# CPLD.net
KiCad netlist of a schematic drawn in Altium Designer
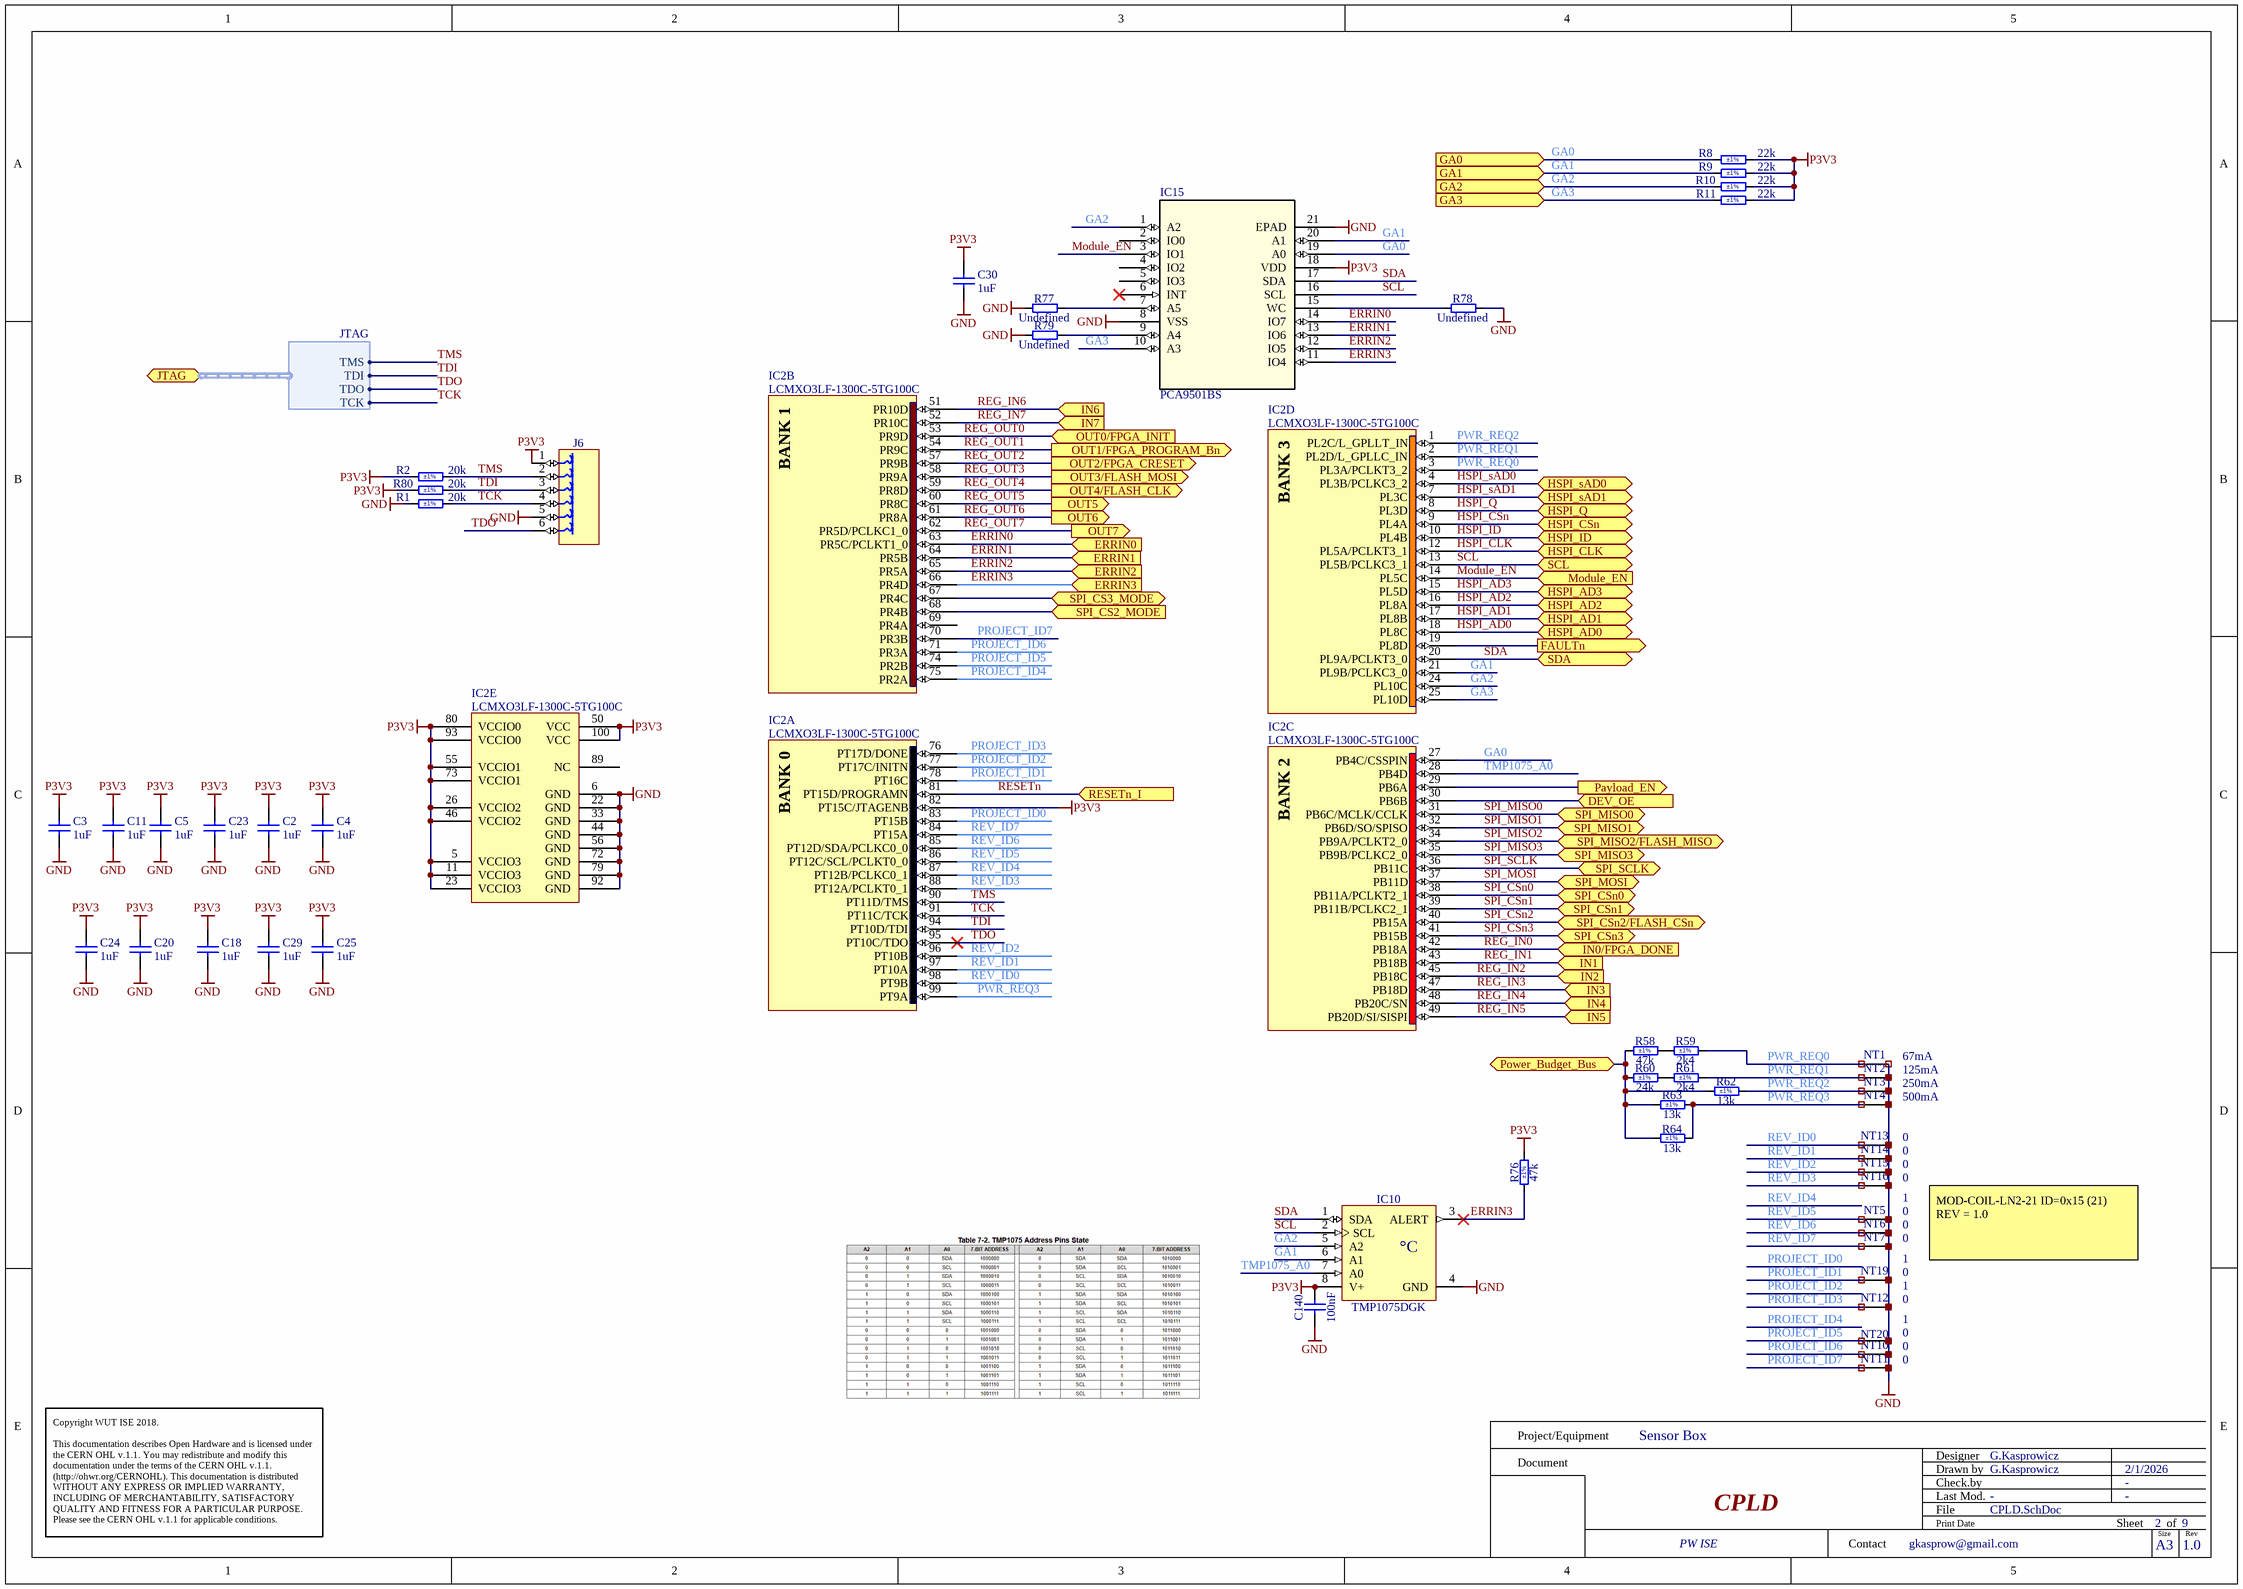
[diagram p0: CPLD.SchDoc]

(export (version "E")
  (design (tool "Eeschema 10.0.6"))
  (components
    (comp (ref "C2")
      (value "1uF")
      (footprint "CAPC1005X55N")
      (description "Non-polarised capacitor")
      (fields
        (field (name "PART NUMBER") "CC0402_1UF_16V_10%_X5R")
        (field (name "VOLTAGE") "16V")
        (field (name "AUTHOR") "CERN DEM JLC")
      )
      (libsource (lib "Capacitors") (part "Capacitor - non polarized"))
    )
    (comp (ref "C3")
      (value "1uF")
      (footprint "CAPC1005X55N")
      (description "Non-polarised capacitor")
      (fields
        (field (name "PART NUMBER") "CC0402_1UF_16V_10%_X5R")
        (field (name "VOLTAGE") "16V")
        (field (name "AUTHOR") "CERN DEM JLC")
      )
      (libsource (lib "Capacitors") (part "Capacitor - non polarized"))
    )
    (comp (ref "C4")
      (value "1uF")
      (footprint "CAPC1005X55N")
      (description "Non-polarised capacitor")
      (fields
        (field (name "PART NUMBER") "CC0402_1UF_16V_10%_X5R")
        (field (name "VOLTAGE") "16V")
        (field (name "AUTHOR") "CERN DEM JLC")
      )
      (libsource (lib "Capacitors") (part "Capacitor - non polarized"))
    )
    (comp (ref "C5")
      (value "1uF")
      (footprint "CAPC1005X55N")
      (description "Non-polarised capacitor")
      (fields
        (field (name "PART NUMBER") "CC0402_1UF_16V_10%_X5R")
        (field (name "VOLTAGE") "16V")
        (field (name "AUTHOR") "CERN DEM JLC")
      )
      (libsource (lib "Capacitors") (part "Capacitor - non polarized"))
    )
    (comp (ref "C11")
      (value "1uF")
      (footprint "CAPC1005X55N")
      (description "Non-polarised capacitor")
      (fields
        (field (name "PART NUMBER") "CC0402_1UF_16V_10%_X5R")
        (field (name "VOLTAGE") "16V")
        (field (name "AUTHOR") "CERN DEM JLC")
      )
      (libsource (lib "Capacitors") (part "Capacitor - non polarized"))
    )
    (comp (ref "C18")
      (value "1uF")
      (footprint "CAPC1005X55N")
      (description "Non-polarised capacitor")
      (fields
        (field (name "PART NUMBER") "CC0402_1UF_16V_10%_X5R")
        (field (name "VOLTAGE") "16V")
        (field (name "AUTHOR") "CERN DEM JLC")
      )
      (libsource (lib "Capacitors") (part "Capacitor - non polarized"))
    )
    (comp (ref "C20")
      (value "1uF")
      (footprint "CAPC1005X55N")
      (description "Non-polarised capacitor")
      (fields
        (field (name "PART NUMBER") "CC0402_1UF_16V_10%_X5R")
        (field (name "VOLTAGE") "16V")
        (field (name "AUTHOR") "CERN DEM JLC")
      )
      (libsource (lib "Capacitors") (part "Capacitor - non polarized"))
    )
    (comp (ref "C23")
      (value "1uF")
      (footprint "CAPC1005X55N")
      (description "Non-polarised capacitor")
      (fields
        (field (name "PART NUMBER") "CC0402_1UF_16V_10%_X5R")
        (field (name "VOLTAGE") "16V")
        (field (name "AUTHOR") "CERN DEM JLC")
      )
      (libsource (lib "Capacitors") (part "Capacitor - non polarized"))
    )
    (comp (ref "C24")
      (value "1uF")
      (footprint "CAPC1005X55N")
      (description "Non-polarised capacitor")
      (fields
        (field (name "PART NUMBER") "CC0402_1UF_16V_10%_X5R")
        (field (name "VOLTAGE") "16V")
        (field (name "AUTHOR") "CERN DEM JLC")
      )
      (libsource (lib "Capacitors") (part "Capacitor - non polarized"))
    )
    (comp (ref "C25")
      (value "1uF")
      (footprint "CAPC1005X55N")
      (description "Non-polarised capacitor")
      (fields
        (field (name "PART NUMBER") "CC0402_1UF_16V_10%_X5R")
        (field (name "VOLTAGE") "16V")
        (field (name "AUTHOR") "CERN DEM JLC")
      )
      (libsource (lib "Capacitors") (part "Capacitor - non polarized"))
    )
    (comp (ref "C29")
      (value "1uF")
      (footprint "CAPC1005X55N")
      (description "Non-polarised capacitor")
      (fields
        (field (name "PART NUMBER") "CC0402_1UF_16V_10%_X5R")
        (field (name "VOLTAGE") "16V")
        (field (name "AUTHOR") "CERN DEM JLC")
      )
      (libsource (lib "Capacitors") (part "Capacitor - non polarized"))
    )
    (comp (ref "C30")
      (value "1uF")
      (footprint "CAPC1005X55N")
      (description "Non-polarised capacitor")
      (fields
        (field (name "PART NUMBER") "CC0402_1UF_16V_10%_X5R")
        (field (name "VOLTAGE") "16V")
        (field (name "AUTHOR") "CERN DEM JLC")
      )
      (libsource (lib "Capacitors") (part "Capacitor - non polarized"))
    )
    (comp (ref "C140")
      (value "100nF")
      (footprint "CAPC1005X55N")
      (description "Non-polarised capacitor")
      (fields
        (field (name "PART NUMBER") "CC0402_100NF_16V_10%_X7R")
        (field (name "VOLTAGE") "16V")
        (field (name "AUTHOR") "CERN DEM JLC")
      )
      (libsource (lib "Capacitors") (part "Capacitor - non polarized"))
    )
    (comp (ref "IC2")
      (value "LCMXO3LF-1300C-5TG100C")
      (footprint "QFP50P1600X1600X160-100N")
      (fields (field (name "MANUFACTURER") "LATTICE SEMICONDUCTOR") (field (name "AUTHOR") "CERN DEM MR"))
      (libsource (lib "ICs And Semiconductors") (part "LCMXO3LF-1300C-5TG100"))
    )
    (comp (ref "IC10")
      (value "TMP1075DGK")
      (footprint "SOP65P490X110-8N")
      (description "High Accuracy Temperature Sensor With I2C and SMBus Interface in Industry Standard LM75")
      (fields (field (name "MANUFACTURER") "TEXAS INSTRUMENTS") (field (name "AUTHOR") "CERN DEM MR"))
      (libsource (lib "ICs And Semiconductors") (part "TMP1075"))
    )
    (comp (ref "IC15")
      (value "PCA9501BS")
      (footprint "HVQFN20_SOT662-1_5X5_NXP")
      (description "8-bit I2C-bus and SMBus I/O port with interrupt, 2-kbit\r\nEEPROM and 6 address pins")
      (fields (field (name "MANUFACTURER") "NXP") (field (name "MANUFACTURER PART NUMBER") "PCA9501BS,118"))
      (libsource (lib "ICs_Analog_Interfaces") (part "IFC_PCA9501BS"))
    )
    (comp (ref "J6")
      (value "TC2030-MCP")
      (footprint "TC2030-MCP")
      (description "TC2030-MCP and TC2030-MCP-NL Pad Contact")
      (fields (field (name "AUTHOR") "CERN DEM HF"))
      (libsource (lib "Eletro-mechanical") (part "TC2030-MCP"))
    )
    (comp (ref "NT1")
      (value "Net Tie")
      (footprint "Net Tie 3")
      (fields (field (name "PART NUMBER") "Net Tie 3") (field (name "AUTHOR") "CERN DEM HF"))
      (libsource (lib "Eletro-mechanical") (part "Net Tie_a"))
    )
    (comp (ref "NT2")
      (value "Net Tie")
      (footprint "Net Tie 3")
      (fields (field (name "PART NUMBER") "Net Tie 3") (field (name "AUTHOR") "CERN DEM HF"))
      (libsource (lib "Eletro-mechanical") (part "Net Tie_a"))
    )
    (comp (ref "NT3")
      (value "Net Tie")
      (footprint "Net Tie 3")
      (fields (field (name "PART NUMBER") "Net Tie 3") (field (name "AUTHOR") "CERN DEM HF"))
      (libsource (lib "Eletro-mechanical") (part "Net Tie_a"))
    )
    (comp (ref "NT4")
      (value "Net Tie")
      (footprint "Net Tie 3")
      (fields (field (name "PART NUMBER") "Net Tie 3") (field (name "AUTHOR") "CERN DEM HF"))
      (libsource (lib "Eletro-mechanical") (part "Net Tie_a"))
    )
    (comp (ref "NT5")
      (value "Net Tie")
      (footprint "Net Tie 3")
      (fields (field (name "PART NUMBER") "Net Tie 3") (field (name "AUTHOR") "CERN DEM HF"))
      (libsource (lib "Eletro-mechanical") (part "Net Tie_a"))
    )
    (comp (ref "NT6")
      (value "Net Tie")
      (footprint "Net Tie 3")
      (fields (field (name "PART NUMBER") "Net Tie 3") (field (name "AUTHOR") "CERN DEM HF"))
      (libsource (lib "Eletro-mechanical") (part "Net Tie_a"))
    )
    (comp (ref "NT7")
      (value "Net Tie")
      (footprint "Net Tie 3")
      (fields (field (name "PART NUMBER") "Net Tie 3") (field (name "AUTHOR") "CERN DEM HF"))
      (libsource (lib "Eletro-mechanical") (part "Net Tie_a"))
    )
    (comp (ref "NT10")
      (value "Net Tie")
      (footprint "Net Tie 3")
      (fields (field (name "PART NUMBER") "Net Tie 3") (field (name "AUTHOR") "CERN DEM HF"))
      (libsource (lib "Eletro-mechanical") (part "Net Tie_a"))
    )
    (comp (ref "NT11")
      (value "Net Tie")
      (footprint "Net Tie 3")
      (fields (field (name "PART NUMBER") "Net Tie 3") (field (name "AUTHOR") "CERN DEM HF"))
      (libsource (lib "Eletro-mechanical") (part "Net Tie_a"))
    )
    (comp (ref "NT12")
      (value "Net Tie")
      (footprint "Net Tie 3")
      (fields (field (name "PART NUMBER") "Net Tie 3") (field (name "AUTHOR") "CERN DEM HF"))
      (libsource (lib "Eletro-mechanical") (part "Net Tie_a"))
    )
    (comp (ref "NT13")
      (value "Net Tie")
      (footprint "Net Tie 3")
      (fields (field (name "PART NUMBER") "Net Tie 3") (field (name "AUTHOR") "CERN DEM HF"))
      (libsource (lib "Eletro-mechanical") (part "Net Tie_a"))
    )
    (comp (ref "NT14")
      (value "Net Tie")
      (footprint "Net Tie 3")
      (fields (field (name "PART NUMBER") "Net Tie 3") (field (name "AUTHOR") "CERN DEM HF"))
      (libsource (lib "Eletro-mechanical") (part "Net Tie_a"))
    )
    (comp (ref "NT15")
      (value "Net Tie")
      (footprint "Net Tie 3")
      (fields (field (name "PART NUMBER") "Net Tie 3") (field (name "AUTHOR") "CERN DEM HF"))
      (libsource (lib "Eletro-mechanical") (part "Net Tie_a"))
    )
    (comp (ref "NT16")
      (value "Net Tie")
      (footprint "Net Tie 3")
      (fields (field (name "PART NUMBER") "Net Tie 3") (field (name "AUTHOR") "CERN DEM HF"))
      (libsource (lib "Eletro-mechanical") (part "Net Tie_a"))
    )
    (comp (ref "NT19")
      (value "Net Tie")
      (footprint "Net Tie 3")
      (fields (field (name "PART NUMBER") "Net Tie 3") (field (name "AUTHOR") "CERN DEM HF"))
      (libsource (lib "Eletro-mechanical") (part "Net Tie_a"))
    )
    (comp (ref "NT20")
      (value "Net Tie")
      (footprint "Net Tie 3")
      (fields (field (name "PART NUMBER") "Net Tie 3") (field (name "AUTHOR") "CERN DEM HF"))
      (libsource (lib "Eletro-mechanical") (part "Net Tie_a"))
    )
    (comp (ref "R1")
      (value "20k")
      (footprint "RESC1005X40N")
      (description "Resistor - 1%")
      (fields
        (field (name "TOLERANCE") "±1%")
        (field (name "PART NUMBER") "R0402_20K_1%_0.0625W_100PPM")
        (field (name "POWER") "0.0625W")
        (field (name "AUTHOR") "CERN DEM JLC")
      )
      (libsource (lib "Resistors") (part "Resistor - 1%"))
    )
    (comp (ref "R2")
      (value "20k")
      (footprint "RESC1005X40N")
      (description "Resistor - 1%")
      (fields
        (field (name "TOLERANCE") "±1%")
        (field (name "PART NUMBER") "R0402_20K_1%_0.0625W_100PPM")
        (field (name "POWER") "0.0625W")
        (field (name "AUTHOR") "CERN DEM JLC")
      )
      (libsource (lib "Resistors") (part "Resistor - 1%"))
    )
    (comp (ref "R8")
      (value "22k")
      (footprint "RESC1005X40N")
      (description "Resistor - 1%")
      (fields
        (field (name "TOLERANCE") "±1%")
        (field (name "PART NUMBER") "R0402_22K_1%_0.0625W_100PPM")
        (field (name "POWER") "0.0625W")
        (field (name "AUTHOR") "CERN DEM JLC")
      )
      (libsource (lib "Resistors") (part "Resistor - 1%"))
    )
    (comp (ref "R9")
      (value "22k")
      (footprint "RESC1005X40N")
      (description "Resistor - 1%")
      (fields
        (field (name "TOLERANCE") "±1%")
        (field (name "PART NUMBER") "R0402_22K_1%_0.0625W_100PPM")
        (field (name "POWER") "0.0625W")
        (field (name "AUTHOR") "CERN DEM JLC")
      )
      (libsource (lib "Resistors") (part "Resistor - 1%"))
    )
    (comp (ref "R10")
      (value "22k")
      (footprint "RESC1005X40N")
      (description "Resistor - 1%")
      (fields
        (field (name "TOLERANCE") "±1%")
        (field (name "PART NUMBER") "R0402_22K_1%_0.0625W_100PPM")
        (field (name "POWER") "0.0625W")
        (field (name "AUTHOR") "CERN DEM JLC")
      )
      (libsource (lib "Resistors") (part "Resistor - 1%"))
    )
    (comp (ref "R11")
      (value "22k")
      (footprint "RESC1005X40N")
      (description "Resistor - 1%")
      (fields
        (field (name "TOLERANCE") "±1%")
        (field (name "PART NUMBER") "R0402_22K_1%_0.0625W_100PPM")
        (field (name "POWER") "0.0625W")
        (field (name "AUTHOR") "CERN DEM JLC")
      )
      (libsource (lib "Resistors") (part "Resistor - 1%"))
    )
    (comp (ref "R58")
      (value "47k")
      (footprint "RESC1005X40N")
      (description "Resistor - 1%")
      (fields
        (field (name "TOLERANCE") "±1%")
        (field (name "PART NUMBER") "R0402_47K_1%_0.0625W_100PPM")
        (field (name "POWER") "0.0625W")
        (field (name "AUTHOR") "CERN DEM JLC")
      )
      (libsource (lib "Resistors") (part "Resistor - 1%"))
    )
    (comp (ref "R59")
      (value "2k4")
      (footprint "RESC1005X40N")
      (description "Resistor - 1%")
      (fields
        (field (name "TOLERANCE") "±1%")
        (field (name "PART NUMBER") "R0402_2K4_1%_0.0625W_100PPM")
        (field (name "POWER") "0.0625W")
        (field (name "AUTHOR") "CERN DEM JLC")
      )
      (libsource (lib "Resistors") (part "Resistor - 1%"))
    )
    (comp (ref "R60")
      (value "24k")
      (footprint "RESC1005X40N")
      (description "Resistor - 1%")
      (fields
        (field (name "TOLERANCE") "±1%")
        (field (name "PART NUMBER") "R0402_24K_1%_0.0625W_100PPM")
        (field (name "POWER") "0.0625W")
        (field (name "AUTHOR") "CERN DEM JLC")
      )
      (libsource (lib "Resistors") (part "Resistor - 1%"))
    )
    (comp (ref "R61")
      (value "2k4")
      (footprint "RESC1005X40N")
      (description "Resistor - 1%")
      (fields
        (field (name "TOLERANCE") "±1%")
        (field (name "PART NUMBER") "R0402_2K4_1%_0.0625W_100PPM")
        (field (name "POWER") "0.0625W")
        (field (name "AUTHOR") "CERN DEM JLC")
      )
      (libsource (lib "Resistors") (part "Resistor - 1%"))
    )
    (comp (ref "R62")
      (value "13k")
      (footprint "RESC1005X40N")
      (description "Resistor - 1%")
      (fields
        (field (name "TOLERANCE") "±1%")
        (field (name "PART NUMBER") "R0402_13K_1%_0.0625W_100PPM")
        (field (name "POWER") "0.0625W")
        (field (name "AUTHOR") "CERN DEM JLC")
      )
      (libsource (lib "Resistors") (part "Resistor - 1%"))
    )
    (comp (ref "R63")
      (value "13k")
      (footprint "RESC1005X40N")
      (description "Resistor - 1%")
      (fields
        (field (name "TOLERANCE") "±1%")
        (field (name "PART NUMBER") "R0402_13K_1%_0.0625W_100PPM")
        (field (name "POWER") "0.0625W")
        (field (name "AUTHOR") "CERN DEM JLC")
      )
      (libsource (lib "Resistors") (part "Resistor - 1%"))
    )
    (comp (ref "R64")
      (value "13k")
      (footprint "RESC1005X40N")
      (description "Resistor - 1%")
      (fields
        (field (name "TOLERANCE") "±1%")
        (field (name "PART NUMBER") "R0402_13K_1%_0.0625W_100PPM")
        (field (name "POWER") "0.0625W")
        (field (name "AUTHOR") "CERN DEM JLC")
      )
      (libsource (lib "Resistors") (part "Resistor - 1%"))
    )
    (comp (ref "R76")
      (value "47k")
      (footprint "RESC1005X40N")
      (description "Resistor - 1%")
      (fields
        (field (name "TOLERANCE") "±1%")
        (field (name "PART NUMBER") "R0402_47K_1%_0.0625W_100PPM")
        (field (name "POWER") "0.0625W")
        (field (name "AUTHOR") "CERN DEM JLC")
      )
      (libsource (lib "Resistors") (part "Resistor - 1%"))
    )
    (comp (ref "R77")
      (value "Undefined")
      (footprint "RESC1005X40N")
      (description "Resistor")
      (fields (field (name "PART NUMBER") "R0402_NO-VALUE") (field (name "AUTHOR") "CERN DEM JLC"))
      (libsource (lib "Resistors") (part "Resistor"))
    )
    (comp (ref "R78")
      (value "Undefined")
      (footprint "RESC1005X40N")
      (description "Resistor")
      (fields (field (name "PART NUMBER") "R0402_NO-VALUE") (field (name "AUTHOR") "CERN DEM JLC"))
      (libsource (lib "Resistors") (part "Resistor"))
    )
    (comp (ref "R79")
      (value "Undefined")
      (footprint "RESC1005X40N")
      (description "Resistor")
      (fields (field (name "PART NUMBER") "R0402_NO-VALUE") (field (name "AUTHOR") "CERN DEM JLC"))
      (libsource (lib "Resistors") (part "Resistor"))
    )
    (comp (ref "R80")
      (value "20k")
      (footprint "RESC1005X40N")
      (description "Resistor - 1%")
      (fields
        (field (name "TOLERANCE") "±1%")
        (field (name "PART NUMBER") "R0402_20K_1%_0.0625W_100PPM")
        (field (name "POWER") "0.0625W")
        (field (name "AUTHOR") "CERN DEM JLC")
      )
      (libsource (lib "Resistors") (part "Resistor - 1%"))
    )
  )
  (nets
    (net (code "2") (name "/DEV_OE") (class "Default")
      (node (ref "IC2") (pin "30") (pinfunction "PB6B_30") (pintype "bidirectional"))
    )
    (net (code "3") (name "/ERRIN0") (class "Default")
      (node (ref "IC15") (pin "14") (pinfunction "IO7_14") (pintype "bidirectional"))
      (node (ref "IC2") (pin "63") (pinfunction "PR5C/PCLKT1_0_63") (pintype "bidirectional"))
    )
    (net (code "4") (name "/ERRIN1") (class "Default")
      (node (ref "IC15") (pin "13") (pinfunction "IO6_13") (pintype "bidirectional"))
      (node (ref "IC2") (pin "64") (pinfunction "PR5B_64") (pintype "bidirectional"))
    )
    (net (code "5") (name "/ERRIN2") (class "Default")
      (node (ref "IC15") (pin "12") (pinfunction "IO5_12") (pintype "bidirectional"))
      (node (ref "IC2") (pin "65") (pinfunction "PR5A_65") (pintype "bidirectional"))
    )
    (net (code "6") (name "/ERRIN3") (class "Default")
      (node (ref "IC10") (pin "3") (pinfunction "ALERT_3") (pintype "output"))
      (node (ref "IC15") (pin "11") (pinfunction "IO4_11") (pintype "bidirectional"))
      (node (ref "IC2") (pin "66") (pinfunction "PR4D_66") (pintype "bidirectional"))
      (node (ref "R76") (pin "1") (pinfunction "1_1") (pintype "passive"))
    )
    (net (code "7") (name "/FAULTn") (class "Default")
      (node (ref "IC2") (pin "19") (pinfunction "PL8D_19") (pintype "bidirectional"))
    )
    (net (code "8") (name "/GA0") (class "Default")
      (node (ref "IC15") (pin "19") (pinfunction "A0_19") (pintype "bidirectional"))
      (node (ref "IC2") (pin "27") (pinfunction "PB4C/CSSPIN_27") (pintype "bidirectional"))
      (node (ref "R8") (pin "2") (pinfunction "2_2") (pintype "passive"))
    )
    (net (code "9") (name "/GA1") (class "Default")
      (node (ref "IC10") (pin "6") (pinfunction "A1_6") (pintype "input"))
      (node (ref "IC15") (pin "20") (pinfunction "A1_20") (pintype "bidirectional"))
      (node (ref "IC2") (pin "21") (pinfunction "PL9B/PCLKC3_0_21") (pintype "bidirectional"))
      (node (ref "R9") (pin "2") (pinfunction "2_2") (pintype "passive"))
    )
    (net (code "10") (name "/GA2") (class "Default")
      (node (ref "IC10") (pin "5") (pinfunction "A2_5") (pintype "input"))
      (node (ref "IC15") (pin "1") (pinfunction "A2_1") (pintype "bidirectional"))
      (node (ref "IC2") (pin "24") (pinfunction "PL10C_24") (pintype "bidirectional"))
      (node (ref "R10") (pin "2") (pinfunction "2_2") (pintype "passive"))
    )
    (net (code "11") (name "/GA3") (class "Default")
      (node (ref "IC15") (pin "10") (pinfunction "A3_10") (pintype "bidirectional"))
      (node (ref "IC2") (pin "25") (pinfunction "PL10D_25") (pintype "bidirectional"))
      (node (ref "R11") (pin "2") (pinfunction "2_2") (pintype "passive"))
    )
    (net (code "12") (name "/HSPI_AD0") (class "Default")
      (node (ref "IC2") (pin "18") (pinfunction "PL8C_18") (pintype "bidirectional"))
    )
    (net (code "13") (name "/HSPI_AD1") (class "Default")
      (node (ref "IC2") (pin "17") (pinfunction "PL8B_17") (pintype "bidirectional"))
    )
    (net (code "14") (name "/HSPI_AD2") (class "Default")
      (node (ref "IC2") (pin "16") (pinfunction "PL8A_16") (pintype "bidirectional"))
    )
    (net (code "15") (name "/HSPI_AD3") (class "Default")
      (node (ref "IC2") (pin "15") (pinfunction "PL5D_15") (pintype "bidirectional"))
    )
    (net (code "16") (name "/HSPI_CLK") (class "Default")
      (node (ref "IC2") (pin "12") (pinfunction "PL5A/PCLKT3_1_12") (pintype "bidirectional"))
    )
    (net (code "17") (name "/HSPI_CSn") (class "Default")
      (node (ref "IC2") (pin "9") (pinfunction "PL4A_9") (pintype "bidirectional"))
    )
    (net (code "18") (name "/HSPI_ID") (class "Default")
      (node (ref "IC2") (pin "10") (pinfunction "PL4B_10") (pintype "bidirectional"))
    )
    (net (code "19") (name "/HSPI_Q") (class "Default")
      (node (ref "IC2") (pin "8") (pinfunction "PL3D_8") (pintype "bidirectional"))
    )
    (net (code "20") (name "/HSPI_sAD0") (class "Default")
      (node (ref "IC2") (pin "4") (pinfunction "PL3B/PCLKC3_2_4") (pintype "bidirectional"))
    )
    (net (code "21") (name "/HSPI_sAD1") (class "Default")
      (node (ref "IC2") (pin "7") (pinfunction "PL3C_7") (pintype "bidirectional"))
    )
    (net (code "22") (name "/Module_EN") (class "Default")
      (node (ref "IC15") (pin "3") (pinfunction "IO1_3") (pintype "bidirectional"))
      (node (ref "IC2") (pin "14") (pinfunction "PL5C_14") (pintype "bidirectional"))
    )
    (net (code "23") (name "/PROJECT_ID0") (class "Default")
      (node (ref "IC2") (pin "83") (pinfunction "PT15B_83") (pintype "bidirectional"))
    )
    (net (code "24") (name "/PROJECT_ID1") (class "Default")
      (node (ref "IC2") (pin "78") (pinfunction "PT16C_78") (pintype "bidirectional"))
      (node (ref "NT19") (pin "1") (pinfunction "1_1") (pintype "bidirectional"))
    )
    (net (code "25") (name "/PROJECT_ID2") (class "Default")
      (node (ref "IC2") (pin "77") (pinfunction "PT17C/INITN_77") (pintype "bidirectional"))
    )
    (net (code "26") (name "/PROJECT_ID3") (class "Default")
      (node (ref "IC2") (pin "76") (pinfunction "PT17D/DONE_76") (pintype "bidirectional"))
      (node (ref "NT12") (pin "1") (pinfunction "1_1") (pintype "bidirectional"))
    )
    (net (code "27") (name "/PROJECT_ID4") (class "Default")
      (node (ref "IC2") (pin "75") (pinfunction "PR2A_75") (pintype "bidirectional"))
    )
    (net (code "28") (name "/PROJECT_ID5") (class "Default")
      (node (ref "IC2") (pin "74") (pinfunction "PR2B_74") (pintype "bidirectional"))
      (node (ref "NT20") (pin "1") (pinfunction "1_1") (pintype "bidirectional"))
    )
    (net (code "29") (name "/PROJECT_ID6") (class "Default")
      (node (ref "IC2") (pin "71") (pinfunction "PR3A_71") (pintype "bidirectional"))
      (node (ref "NT10") (pin "1") (pinfunction "1_1") (pintype "bidirectional"))
    )
    (net (code "30") (name "/PROJECT_ID7") (class "Default")
      (node (ref "IC2") (pin "70") (pinfunction "PR3B_70") (pintype "bidirectional"))
      (node (ref "NT11") (pin "1") (pinfunction "1_1") (pintype "bidirectional"))
    )
    (net (code "31") (name "/PWR_REQ0") (class "Default")
      (node (ref "IC2") (pin "3") (pinfunction "PL3A/PCLKT3_2_3") (pintype "bidirectional"))
      (node (ref "NT1") (pin "1") (pinfunction "1_1") (pintype "bidirectional"))
      (node (ref "R59") (pin "2") (pinfunction "2_2") (pintype "passive"))
    )
    (net (code "32") (name "/PWR_REQ1") (class "Default")
      (node (ref "IC2") (pin "2") (pinfunction "PL2D/L_GPLLC_IN_2") (pintype "bidirectional"))
      (node (ref "NT2") (pin "1") (pinfunction "1_1") (pintype "bidirectional"))
      (node (ref "R61") (pin "2") (pinfunction "2_2") (pintype "passive"))
    )
    (net (code "33") (name "/PWR_REQ2") (class "Default")
      (node (ref "IC2") (pin "1") (pinfunction "PL2C/L_GPLLT_IN_1") (pintype "bidirectional"))
      (node (ref "NT3") (pin "1") (pinfunction "1_1") (pintype "bidirectional"))
      (node (ref "R62") (pin "2") (pinfunction "2_2") (pintype "passive"))
    )
    (net (code "34") (name "/PWR_REQ3") (class "Default")
      (node (ref "IC2") (pin "99") (pinfunction "PT9A_99") (pintype "bidirectional"))
      (node (ref "NT4") (pin "1") (pinfunction "1_1") (pintype "bidirectional"))
      (node (ref "R63") (pin "2") (pinfunction "2_2") (pintype "passive"))
      (node (ref "R64") (pin "2") (pinfunction "2_2") (pintype "passive"))
    )
    (net (code "35") (name "/Payload_EN") (class "Default")
      (node (ref "IC2") (pin "29") (pinfunction "PB6A_29") (pintype "bidirectional"))
    )
    (net (code "36") (name "/Power_Budget_Bus") (class "Default")
      (node (ref "R58") (pin "1") (pinfunction "1_1") (pintype "passive"))
      (node (ref "R60") (pin "1") (pinfunction "1_1") (pintype "passive"))
      (node (ref "R62") (pin "1") (pinfunction "1_1") (pintype "passive"))
      (node (ref "R63") (pin "1") (pinfunction "1_1") (pintype "passive"))
      (node (ref "R64") (pin "1") (pinfunction "1_1") (pintype "passive"))
    )
    (net (code "37") (name "/REG_IN0") (class "Default")
      (node (ref "IC2") (pin "42") (pinfunction "PB18A_42") (pintype "bidirectional"))
    )
    (net (code "38") (name "/REG_IN1") (class "Default")
      (node (ref "IC2") (pin "43") (pinfunction "PB18B_43") (pintype "bidirectional"))
    )
    (net (code "39") (name "/REG_IN2") (class "Default")
      (node (ref "IC2") (pin "45") (pinfunction "PB18C_45") (pintype "bidirectional"))
    )
    (net (code "40") (name "/REG_IN3") (class "Default")
      (node (ref "IC2") (pin "47") (pinfunction "PB18D_47") (pintype "bidirectional"))
    )
    (net (code "41") (name "/REG_IN4") (class "Default")
      (node (ref "IC2") (pin "48") (pinfunction "PB20C/SN_48") (pintype "bidirectional"))
    )
    (net (code "42") (name "/REG_IN5") (class "Default")
      (node (ref "IC2") (pin "49") (pinfunction "PB20D/SI/SISPI_49") (pintype "bidirectional"))
    )
    (net (code "43") (name "/REG_IN6") (class "Default")
      (node (ref "IC2") (pin "51") (pinfunction "PR10D_51") (pintype "bidirectional"))
    )
    (net (code "44") (name "/REG_IN7") (class "Default")
      (node (ref "IC2") (pin "52") (pinfunction "PR10C_52") (pintype "bidirectional"))
    )
    (net (code "45") (name "/REG_OUT0") (class "Default")
      (node (ref "IC2") (pin "53") (pinfunction "PR9D_53") (pintype "bidirectional"))
    )
    (net (code "46") (name "/REG_OUT1") (class "Default")
      (node (ref "IC2") (pin "54") (pinfunction "PR9C_54") (pintype "bidirectional"))
    )
    (net (code "47") (name "/REG_OUT2") (class "Default")
      (node (ref "IC2") (pin "57") (pinfunction "PR9B_57") (pintype "bidirectional"))
    )
    (net (code "48") (name "/REG_OUT3") (class "Default")
      (node (ref "IC2") (pin "58") (pinfunction "PR9A_58") (pintype "bidirectional"))
    )
    (net (code "49") (name "/REG_OUT4") (class "Default")
      (node (ref "IC2") (pin "59") (pinfunction "PR8D_59") (pintype "bidirectional"))
    )
    (net (code "50") (name "/REG_OUT5") (class "Default")
      (node (ref "IC2") (pin "60") (pinfunction "PR8C_60") (pintype "bidirectional"))
    )
    (net (code "51") (name "/REG_OUT6") (class "Default")
      (node (ref "IC2") (pin "61") (pinfunction "PR8A_61") (pintype "bidirectional"))
    )
    (net (code "52") (name "/REG_OUT7") (class "Default")
      (node (ref "IC2") (pin "62") (pinfunction "PR5D/PCLKC1_0_62") (pintype "bidirectional"))
    )
    (net (code "53") (name "/RESETn") (class "Default")
      (node (ref "IC2") (pin "81") (pinfunction "PT15D/PROGRAMN_81") (pintype "bidirectional"))
    )
    (net (code "54") (name "/REV_ID0") (class "Default")
      (node (ref "IC2") (pin "98") (pinfunction "PT9B_98") (pintype "bidirectional"))
      (node (ref "NT13") (pin "1") (pinfunction "1_1") (pintype "bidirectional"))
    )
    (net (code "55") (name "/REV_ID1") (class "Default")
      (node (ref "IC2") (pin "97") (pinfunction "PT10A_97") (pintype "bidirectional"))
      (node (ref "NT14") (pin "1") (pinfunction "1_1") (pintype "bidirectional"))
    )
    (net (code "56") (name "/REV_ID2") (class "Default")
      (node (ref "IC2") (pin "96") (pinfunction "PT10B_96") (pintype "bidirectional"))
      (node (ref "NT15") (pin "1") (pinfunction "1_1") (pintype "bidirectional"))
    )
    (net (code "57") (name "/REV_ID3") (class "Default")
      (node (ref "IC2") (pin "88") (pinfunction "PT12A/PCLKT0_1_88") (pintype "bidirectional"))
      (node (ref "NT16") (pin "1") (pinfunction "1_1") (pintype "bidirectional"))
    )
    (net (code "58") (name "/REV_ID4") (class "Default")
      (node (ref "IC2") (pin "87") (pinfunction "PT12B/PCLKC0_1_87") (pintype "bidirectional"))
    )
    (net (code "59") (name "/REV_ID5") (class "Default")
      (node (ref "IC2") (pin "86") (pinfunction "PT12C/SCL/PCLKT0_0_86") (pintype "bidirectional"))
      (node (ref "NT5") (pin "1") (pinfunction "1_1") (pintype "bidirectional"))
    )
    (net (code "60") (name "/REV_ID6") (class "Default")
      (node (ref "IC2") (pin "85") (pinfunction "PT12D/SDA/PCLKC0_0_85") (pintype "bidirectional"))
      (node (ref "NT6") (pin "1") (pinfunction "1_1") (pintype "bidirectional"))
    )
    (net (code "61") (name "/REV_ID7") (class "Default")
      (node (ref "IC2") (pin "84") (pinfunction "PT15A_84") (pintype "bidirectional"))
      (node (ref "NT7") (pin "1") (pinfunction "1_1") (pintype "bidirectional"))
    )
    (net (code "62") (name "/SCL") (class "Default")
      (node (ref "IC10") (pin "2") (pinfunction "SCL_2") (pintype "input"))
      (node (ref "IC15") (pin "16") (pinfunction "SCL_16") (pintype "passive"))
      (node (ref "IC2") (pin "13") (pinfunction "PL5B/PCLKC3_1_13") (pintype "bidirectional"))
    )
    (net (code "63") (name "/SDA") (class "Default")
      (node (ref "IC10") (pin "1") (pinfunction "SDA_1") (pintype "bidirectional"))
      (node (ref "IC15") (pin "17") (pinfunction "SDA_17") (pintype "passive"))
      (node (ref "IC2") (pin "20") (pinfunction "PL9A/PCLKT3_0_20") (pintype "bidirectional"))
    )
    (net (code "64") (name "/SPI_CS2_MODE") (class "Default")
      (node (ref "IC2") (pin "68") (pinfunction "PR4B_68") (pintype "bidirectional"))
    )
    (net (code "65") (name "/SPI_CS3_MODE") (class "Default")
      (node (ref "IC2") (pin "67") (pinfunction "PR4C_67") (pintype "bidirectional"))
    )
    (net (code "66") (name "/SPI_CSn0") (class "Default")
      (node (ref "IC2") (pin "38") (pinfunction "PB11A/PCLKT2_1_38") (pintype "bidirectional"))
    )
    (net (code "67") (name "/SPI_CSn1") (class "Default")
      (node (ref "IC2") (pin "39") (pinfunction "PB11B/PCLKC2_1_39") (pintype "bidirectional"))
    )
    (net (code "68") (name "/SPI_CSn2") (class "Default")
      (node (ref "IC2") (pin "40") (pinfunction "PB15A_40") (pintype "bidirectional"))
    )
    (net (code "69") (name "/SPI_CSn3") (class "Default")
      (node (ref "IC2") (pin "41") (pinfunction "PB15B_41") (pintype "bidirectional"))
    )
    (net (code "70") (name "/SPI_MISO0") (class "Default")
      (node (ref "IC2") (pin "31") (pinfunction "PB6C/MCLK/CCLK_31") (pintype "bidirectional"))
    )
    (net (code "71") (name "/SPI_MISO1") (class "Default")
      (node (ref "IC2") (pin "32") (pinfunction "PB6D/SO/SPISO_32") (pintype "bidirectional"))
    )
    (net (code "72") (name "/SPI_MISO2") (class "Default")
      (node (ref "IC2") (pin "34") (pinfunction "PB9A/PCLKT2_0_34") (pintype "bidirectional"))
    )
    (net (code "73") (name "/SPI_MISO3") (class "Default")
      (node (ref "IC2") (pin "35") (pinfunction "PB9B/PCLKC2_0_35") (pintype "bidirectional"))
    )
    (net (code "74") (name "/SPI_MOSI") (class "Default")
      (node (ref "IC2") (pin "37") (pinfunction "PB11D_37") (pintype "bidirectional"))
    )
    (net (code "75") (name "/SPI_SCLK") (class "Default")
      (node (ref "IC2") (pin "36") (pinfunction "PB11C_36") (pintype "bidirectional"))
    )
    (net (code "76") (name "/TCK") (class "Default")
      (node (ref "IC2") (pin "91") (pinfunction "PT11C/TCK_91") (pintype "bidirectional"))
      (node (ref "J6") (pin "4") (pinfunction "4_4") (pintype "bidirectional"))
      (node (ref "R1") (pin "1") (pinfunction "1_1") (pintype "passive"))
    )
    (net (code "77") (name "/TDI") (class "Default")
      (node (ref "IC2") (pin "94") (pinfunction "PT10D/TDI_94") (pintype "bidirectional"))
      (node (ref "J6") (pin "3") (pinfunction "3_3") (pintype "bidirectional"))
      (node (ref "R80") (pin "1") (pinfunction "1_1") (pintype "passive"))
    )
    (net (code "78") (name "/TDO") (class "Default")
      (node (ref "IC2") (pin "95") (pinfunction "PT10C/TDO_95") (pintype "bidirectional"))
      (node (ref "J6") (pin "6") (pinfunction "6_6") (pintype "bidirectional"))
    )
    (net (code "79") (name "/TMP1075_A0") (class "Default")
      (node (ref "IC10") (pin "7") (pinfunction "A0_7") (pintype "input"))
      (node (ref "IC2") (pin "28") (pinfunction "PB4D_28") (pintype "bidirectional"))
    )
    (net (code "80") (name "/TMS") (class "Default")
      (node (ref "IC2") (pin "90") (pinfunction "PT11D/TMS_90") (pintype "bidirectional"))
      (node (ref "J6") (pin "2") (pinfunction "2_2") (pintype "bidirectional"))
      (node (ref "R2") (pin "1") (pinfunction "1_1") (pintype "passive"))
    )
    (net (code "82") (name "GND") (class "Default")
      (node (ref "C11") (pin "1") (pinfunction "1_1") (pintype "passive"))
      (node (ref "C140") (pin "1") (pinfunction "1_1") (pintype "passive"))
      (node (ref "C18") (pin "1") (pinfunction "1_1") (pintype "passive"))
      (node (ref "C2") (pin "1") (pinfunction "1_1") (pintype "passive"))
      (node (ref "C20") (pin "1") (pinfunction "1_1") (pintype "passive"))
      (node (ref "C23") (pin "1") (pinfunction "1_1") (pintype "passive"))
      (node (ref "C24") (pin "1") (pinfunction "1_1") (pintype "passive"))
      (node (ref "C25") (pin "1") (pinfunction "1_1") (pintype "passive"))
      (node (ref "C29") (pin "1") (pinfunction "1_1") (pintype "passive"))
      (node (ref "C3") (pin "1") (pinfunction "1_1") (pintype "passive"))
      (node (ref "C30") (pin "1") (pinfunction "1_1") (pintype "passive"))
      (node (ref "C4") (pin "1") (pinfunction "1_1") (pintype "passive"))
      (node (ref "C5") (pin "1") (pinfunction "1_1") (pintype "passive"))
      (node (ref "IC10") (pin "4") (pinfunction "GND_4") (pintype "power_in"))
      (node (ref "IC15") (pin "21") (pinfunction "EPAD_21") (pintype "passive"))
      (node (ref "IC15") (pin "8") (pinfunction "VSS_8") (pintype "power_in"))
      (node (ref "IC2") (pin "22") (pinfunction "GND_22") (pintype "power_in"))
      (node (ref "IC2") (pin "33") (pinfunction "GND_33") (pintype "power_in"))
      (node (ref "IC2") (pin "44") (pinfunction "GND_44") (pintype "power_in"))
      (node (ref "IC2") (pin "56") (pinfunction "GND_56") (pintype "power_in"))
      (node (ref "IC2") (pin "6") (pinfunction "GND_6") (pintype "power_in"))
      (node (ref "IC2") (pin "72") (pinfunction "GND_72") (pintype "power_in"))
      (node (ref "IC2") (pin "79") (pinfunction "GND_79") (pintype "power_in"))
      (node (ref "IC2") (pin "92") (pinfunction "GND_92") (pintype "power_in"))
      (node (ref "J6") (pin "5") (pinfunction "5_5") (pintype "bidirectional"))
      (node (ref "NT1") (pin "2") (pinfunction "2_2") (pintype "bidirectional"))
      (node (ref "NT10") (pin "2") (pinfunction "2_2") (pintype "bidirectional"))
      (node (ref "NT11") (pin "2") (pinfunction "2_2") (pintype "bidirectional"))
      (node (ref "NT12") (pin "2") (pinfunction "2_2") (pintype "bidirectional"))
      (node (ref "NT13") (pin "2") (pinfunction "2_2") (pintype "bidirectional"))
      (node (ref "NT14") (pin "2") (pinfunction "2_2") (pintype "bidirectional"))
      (node (ref "NT15") (pin "2") (pinfunction "2_2") (pintype "bidirectional"))
      (node (ref "NT16") (pin "2") (pinfunction "2_2") (pintype "bidirectional"))
      (node (ref "NT19") (pin "2") (pinfunction "2_2") (pintype "bidirectional"))
      (node (ref "NT2") (pin "2") (pinfunction "2_2") (pintype "bidirectional"))
      (node (ref "NT20") (pin "2") (pinfunction "2_2") (pintype "bidirectional"))
      (node (ref "NT3") (pin "2") (pinfunction "2_2") (pintype "bidirectional"))
      (node (ref "NT4") (pin "2") (pinfunction "2_2") (pintype "bidirectional"))
      (node (ref "NT5") (pin "2") (pinfunction "2_2") (pintype "bidirectional"))
      (node (ref "NT6") (pin "2") (pinfunction "2_2") (pintype "bidirectional"))
      (node (ref "NT7") (pin "2") (pinfunction "2_2") (pintype "bidirectional"))
      (node (ref "R1") (pin "2") (pinfunction "2_2") (pintype "passive"))
      (node (ref "R77") (pin "1") (pinfunction "1_1") (pintype "passive"))
      (node (ref "R78") (pin "2") (pinfunction "2_2") (pintype "passive"))
      (node (ref "R79") (pin "1") (pinfunction "1_1") (pintype "passive"))
    )
    (net (code "83") (name "Net-(IC15-A4)") (class "Default")
      (node (ref "IC15") (pin "9") (pinfunction "A4_9") (pintype "bidirectional"))
      (node (ref "R79") (pin "2") (pinfunction "2_2") (pintype "passive"))
    )
    (net (code "84") (name "Net-(IC15-A5)") (class "Default")
      (node (ref "IC15") (pin "7") (pinfunction "A5_7") (pintype "bidirectional"))
      (node (ref "R77") (pin "2") (pinfunction "2_2") (pintype "passive"))
    )
    (net (code "85") (name "Net-(IC15-WC)") (class "Default")
      (node (ref "IC15") (pin "15") (pinfunction "WC_15") (pintype "passive"))
      (node (ref "R78") (pin "1") (pinfunction "1_1") (pintype "passive"))
    )
    (net (code "86") (name "Net-(R58-Pad2)") (class "Default")
      (node (ref "R58") (pin "2") (pinfunction "2_2") (pintype "passive"))
      (node (ref "R59") (pin "1") (pinfunction "1_1") (pintype "passive"))
    )
    (net (code "87") (name "Net-(R60-Pad2)") (class "Default")
      (node (ref "R60") (pin "2") (pinfunction "2_2") (pintype "passive"))
      (node (ref "R61") (pin "1") (pinfunction "1_1") (pintype "passive"))
    )
    (net (code "88") (name "P3V3") (class "Default")
      (node (ref "C11") (pin "2") (pinfunction "2_2") (pintype "passive"))
      (node (ref "C140") (pin "2") (pinfunction "2_2") (pintype "passive"))
      (node (ref "C18") (pin "2") (pinfunction "2_2") (pintype "passive"))
      (node (ref "C2") (pin "2") (pinfunction "2_2") (pintype "passive"))
      (node (ref "C20") (pin "2") (pinfunction "2_2") (pintype "passive"))
      (node (ref "C23") (pin "2") (pinfunction "2_2") (pintype "passive"))
      (node (ref "C24") (pin "2") (pinfunction "2_2") (pintype "passive"))
      (node (ref "C25") (pin "2") (pinfunction "2_2") (pintype "passive"))
      (node (ref "C29") (pin "2") (pinfunction "2_2") (pintype "passive"))
      (node (ref "C3") (pin "2") (pinfunction "2_2") (pintype "passive"))
      (node (ref "C30") (pin "2") (pinfunction "2_2") (pintype "passive"))
      (node (ref "C4") (pin "2") (pinfunction "2_2") (pintype "passive"))
      (node (ref "C5") (pin "2") (pinfunction "2_2") (pintype "passive"))
      (node (ref "IC10") (pin "8") (pinfunction "V+_8") (pintype "power_in"))
      (node (ref "IC15") (pin "18") (pinfunction "VDD_18") (pintype "power_in"))
      (node (ref "IC2") (pin "100") (pinfunction "VCC_100") (pintype "power_in"))
      (node (ref "IC2") (pin "11") (pinfunction "VCCIO3_11") (pintype "power_in"))
      (node (ref "IC2") (pin "23") (pinfunction "VCCIO3_23") (pintype "power_in"))
      (node (ref "IC2") (pin "26") (pinfunction "VCCIO2_26") (pintype "power_in"))
      (node (ref "IC2") (pin "46") (pinfunction "VCCIO2_46") (pintype "power_in"))
      (node (ref "IC2") (pin "5") (pinfunction "VCCIO3_5") (pintype "power_in"))
      (node (ref "IC2") (pin "50") (pinfunction "VCC_50") (pintype "power_in"))
      (node (ref "IC2") (pin "55") (pinfunction "VCCIO1_55") (pintype "power_in"))
      (node (ref "IC2") (pin "73") (pinfunction "VCCIO1_73") (pintype "power_in"))
      (node (ref "IC2") (pin "80") (pinfunction "VCCIO0_80") (pintype "power_in"))
      (node (ref "IC2") (pin "82") (pinfunction "PT15C/JTAGENB_82") (pintype "bidirectional"))
      (node (ref "IC2") (pin "93") (pinfunction "VCCIO0_93") (pintype "power_in"))
      (node (ref "J6") (pin "1") (pinfunction "1_1") (pintype "bidirectional"))
      (node (ref "R10") (pin "1") (pinfunction "1_1") (pintype "passive"))
      (node (ref "R11") (pin "1") (pinfunction "1_1") (pintype "passive"))
      (node (ref "R2") (pin "2") (pinfunction "2_2") (pintype "passive"))
      (node (ref "R76") (pin "2") (pinfunction "2_2") (pintype "passive"))
      (node (ref "R8") (pin "1") (pinfunction "1_1") (pintype "passive"))
      (node (ref "R80") (pin "2") (pinfunction "2_2") (pintype "passive"))
      (node (ref "R9") (pin "1") (pinfunction "1_1") (pintype "passive"))
    )
    (net (code "89") (name "unconnected-(IC2B-PR4A-Pad69)") (class "Default")
      (node (ref "IC2") (pin "69") (pinfunction "PR4A_69") (pintype "bidirectional"))
    )
    (net (code "90") (name "unconnected-(IC2E-NC-Pad89)") (class "Default")
      (node (ref "IC2") (pin "89") (pinfunction "NC_89") (pintype "passive"))
    )
    (net (code "91") (name "unconnected-(IC15-INT-Pad6)") (class "Default")
      (node (ref "IC15") (pin "6") (pinfunction "INT_6") (pintype "input+no_connect"))
    )
    (net (code "92") (name "unconnected-(IC15-IO0-Pad2)") (class "Default")
      (node (ref "IC15") (pin "2") (pinfunction "IO0_2") (pintype "bidirectional"))
    )
    (net (code "93") (name "unconnected-(IC15-IO2-Pad4)") (class "Default")
      (node (ref "IC15") (pin "4") (pinfunction "IO2_4") (pintype "bidirectional"))
    )
    (net (code "94") (name "unconnected-(IC15-IO3-Pad5)") (class "Default")
      (node (ref "IC15") (pin "5") (pinfunction "IO3_5") (pintype "bidirectional"))
    )
  )
)
